# SH1_-_POWER.net
KiCad netlist of a schematic drawn in Altium Designer
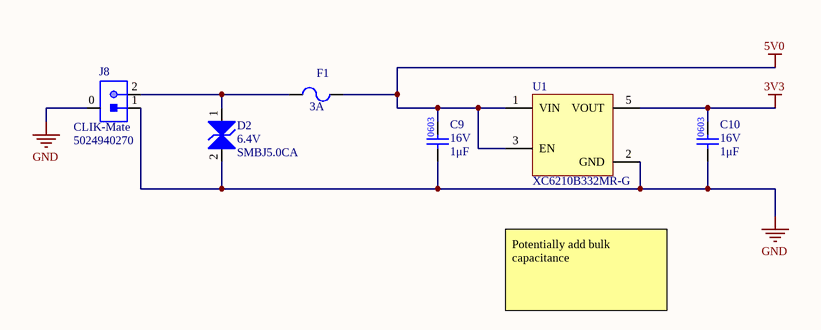
[diagram p0: SH1 - POWER.SchDoc]

(export (version "E")
  (design (tool "Eeschema 10.0.6"))
  (components
    (comp (ref "C9")
      (value "1μF")
      (footprint "CAP0603")
      (description "CAP CER 1UF 16V Y5V 0603")
      (fields (field (name "VOLTAGE RATING") "16V") (field (name "Comment") "CAP_1uF_16V_0603"))
      (libsource (lib "UWRT_Schematic_Library_2020") (part "CAP_1uF_16V_0603"))
    )
    (comp (ref "C10")
      (value "1μF")
      (footprint "CAP0603")
      (description "CAP CER 1UF 16V Y5V 0603")
      (fields (field (name "VOLTAGE RATING") "16V") (field (name "Comment") "CAP_1uF_16V_0603"))
      (libsource (lib "UWRT_Schematic_Library_2020") (part "CAP_1uF_16V_0603"))
    )
    (comp (ref "D2")
      (value "TVS_DIODE_BIDIR_5V")
      (footprint "TVS_DIODE_BIDIR_SMB")
      (description "TVS DIODE 5V 9.2V SMB")
      (fields
        (field (name "VOLTAGE - BREAKDOWN (MIN)") "6.4V")
        (field (name "MANUFACTURER PART NUMBER 1") "SMBJ5.0CA")
      )
      (libsource (lib "UWRT_Schematic_Library_2020") (part "TVS_DIODE_BIDIR_5V"))
    )
    (comp (ref "F1")
      (value "FUSE_3A_0603")
      (footprint "FUSE_0603")
      (description "FUSE SMD 3A 32V 0603")
      (libsource (lib "UWRT_Schematic_Library_2020") (part "FUSE_3A_0603"))
    )
    (comp (ref "J8")
      (value "CON_2M_SM_RA")
      (footprint "MOLEX-5024940270")
      (description "CONN HEADER SMD RIGHT ANGLE 2MM PITCH")
      (fields (field (name "FAMILY") "CLIK-Mate") (field (name "MANUFACTURER PART NUMBER 1") "5024940270"))
      (libsource (lib "UWRT_Schematic_Library_2020") (part "CON_2M_SM_RA"))
    )
    (comp (ref "U1")
      (value "LDO_3.3V_700mA")
      (footprint "SOT95P285X140-5N")
      (description "IC REG LINEAR 3.3V 700MA SOT25")
      (fields (field (name "MANUFACTURER PART NUMBER 1") "XC6210B332MR-G"))
      (libsource (lib "UWRT_Schematic_Library_2020") (part "LDO_3.3V_700mA"))
    )
  )
  (nets
    (net (code "1") (name "3V3") (class "Default")
      (node (ref "C10") (pin "2") (pinfunction "2_2") (pintype "passive"))
      (node (ref "U1") (pin "5") (pinfunction "VOUT_5") (pintype "passive"))
    )
    (net (code "2") (name "5V0") (class "Default")
      (node (ref "C9") (pin "2") (pinfunction "2_2") (pintype "passive"))
      (node (ref "F1") (pin "2") (pinfunction "2_2") (pintype "passive"))
      (node (ref "U1") (pin "1") (pinfunction "VIN_1") (pintype "passive"))
      (node (ref "U1") (pin "3") (pinfunction "EN_3") (pintype "passive"))
    )
    (net (code "3") (name "GND") (class "Default")
      (node (ref "C10") (pin "1") (pinfunction "1_1") (pintype "passive"))
      (node (ref "C9") (pin "1") (pinfunction "1_1") (pintype "passive"))
      (node (ref "D2") (pin "2") (pinfunction "2_2") (pintype "passive"))
      (node (ref "J8") (pin "0") (pinfunction "0_0") (pintype "passive"))
      (node (ref "J8") (pin "1") (pinfunction "1_1") (pintype "passive"))
      (node (ref "U1") (pin "2") (pinfunction "GND_2") (pintype "passive"))
    )
    (net (code "4") (name "Net-(D2-Pad1)") (class "Default")
      (node (ref "D2") (pin "1") (pinfunction "1_1") (pintype "passive"))
      (node (ref "F1") (pin "1") (pinfunction "1_1") (pintype "passive"))
      (node (ref "J8") (pin "2") (pinfunction "2_2") (pintype "passive"))
    )
  )
)
